# ETH-PHY.net
KiCad netlist of a schematic drawn in Altium Designer
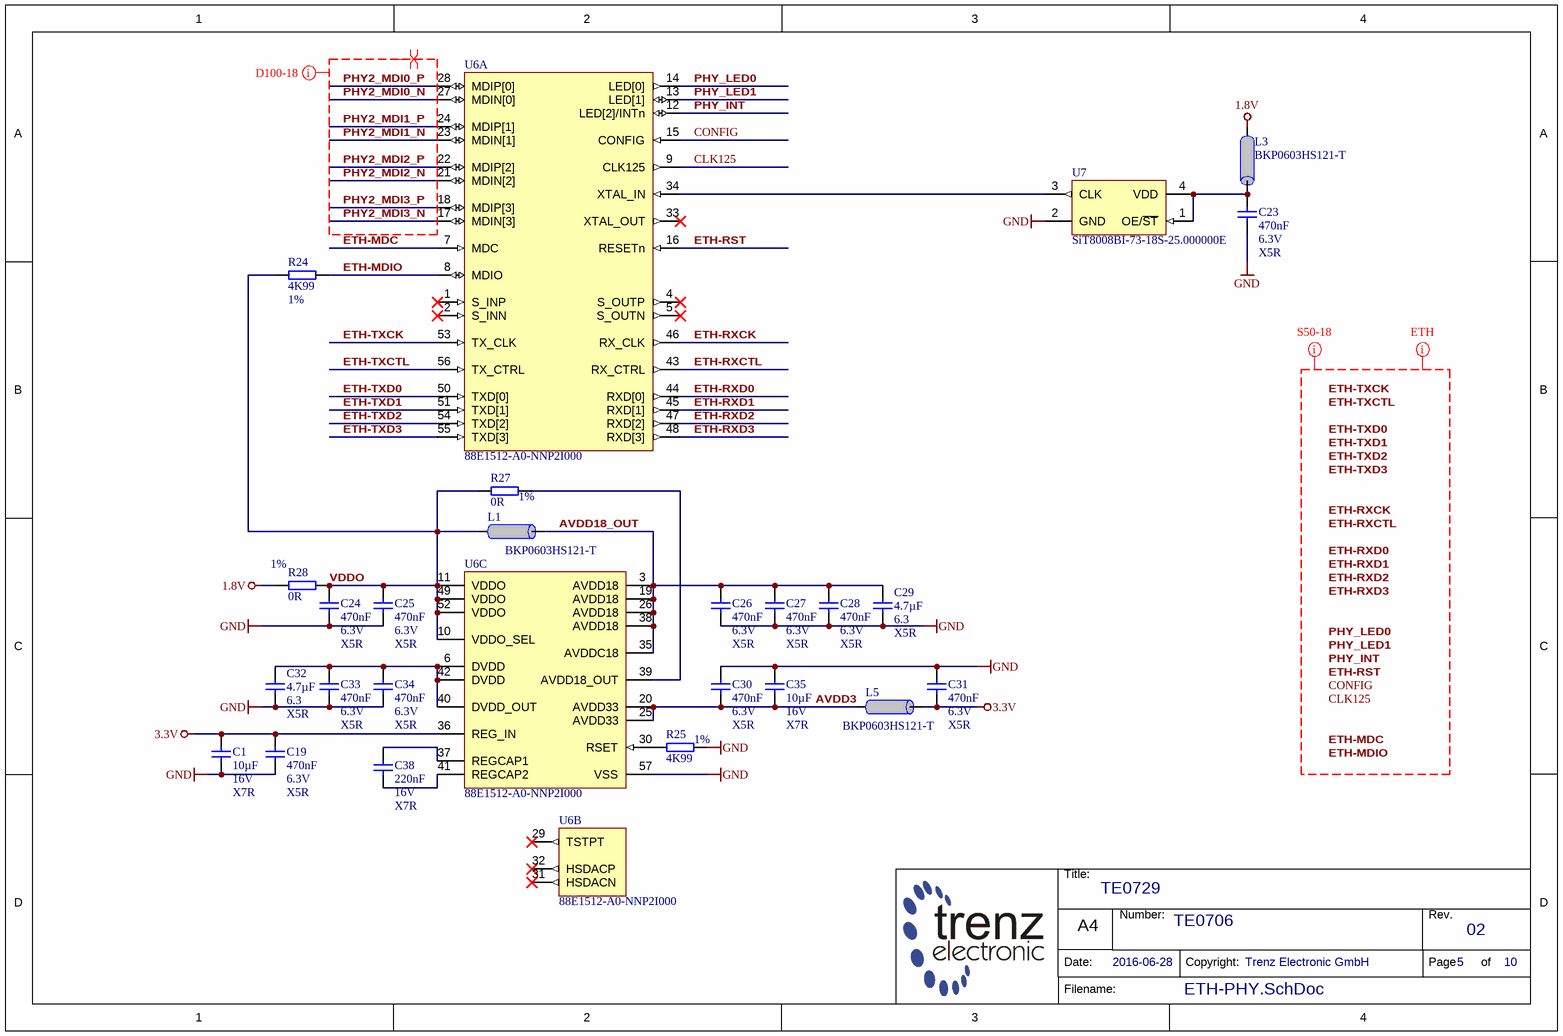
[diagram p0: ETH-PHY.SchDoc]

(export (version "E")
  (design (tool "Eeschema 10.0.6"))
  (components
    (comp (ref "C1")
      (value "10µF")
      (footprint "CAPC2012X135N")
      (description "KON 10µF 16V X7R SMD 10%")
      (fields
        (field (name "VOLTAGE") "16V")
        (field (name "TECHNOLOGY") "X7R")
        (field (name "TOLERANCE") "10%")
      )
      (libsource (lib "TE") (part "CAP-NP"))
    )
    (comp (ref "C19")
      (value "470nF")
      (footprint "CAPC1005X55N")
      (description "KON 470nF 6,3V X5R SMD")
      (fields (field (name "VOLTAGE") "6.3V") (field (name "TECHNOLOGY") "X5R"))
      (libsource (lib "TE") (part "CAP-NP"))
    )
    (comp (ref "C23")
      (value "470nF")
      (footprint "CAPC1005X55N")
      (description "KON 470nF 6,3V X5R SMD")
      (fields (field (name "VOLTAGE") "6.3V") (field (name "TECHNOLOGY") "X5R"))
      (libsource (lib "TE") (part "CAP-NP"))
    )
    (comp (ref "C24")
      (value "470nF")
      (footprint "CAPC1005X55N")
      (description "KON 470nF 6,3V X5R SMD")
      (fields (field (name "VOLTAGE") "6.3V") (field (name "TECHNOLOGY") "X5R"))
      (libsource (lib "TE") (part "CAP-NP"))
    )
    (comp (ref "C25")
      (value "470nF")
      (footprint "CAPC1005X55N")
      (description "KON 470nF 6,3V X5R SMD")
      (fields (field (name "VOLTAGE") "6.3V") (field (name "TECHNOLOGY") "X5R"))
      (libsource (lib "TE") (part "CAP-NP"))
    )
    (comp (ref "C26")
      (value "470nF")
      (footprint "CAPC1005X55N")
      (description "KON 470nF 6,3V X5R SMD")
      (fields (field (name "VOLTAGE") "6.3V") (field (name "TECHNOLOGY") "X5R"))
      (libsource (lib "TE") (part "CAP-NP"))
    )
    (comp (ref "C27")
      (value "470nF")
      (footprint "CAPC1005X55N")
      (description "KON 470nF 6,3V X5R SMD")
      (fields (field (name "VOLTAGE") "6.3V") (field (name "TECHNOLOGY") "X5R"))
      (libsource (lib "TE") (part "CAP-NP"))
    )
    (comp (ref "C28")
      (value "470nF")
      (footprint "CAPC1005X55N")
      (description "KON 470nF 6,3V X5R SMD")
      (fields (field (name "VOLTAGE") "6.3V") (field (name "TECHNOLOGY") "X5R"))
      (libsource (lib "TE") (part "CAP-NP"))
    )
    (comp (ref "C29")
      (value "4.7µF")
      (footprint "CAPC1005X60N")
      (description "KON 4.7µF 6.3V X5R SMD 20%")
      (fields
        (field (name "VOLTAGE") "6.3")
        (field (name "TECHNOLOGY") "X5R")
        (field (name "TOLERANCE") "20%")
      )
      (libsource (lib "TE") (part "CAP-NP"))
    )
    (comp (ref "C30")
      (value "470nF")
      (footprint "CAPC1005X55N")
      (description "KON 470nF 6,3V X5R SMD")
      (fields (field (name "VOLTAGE") "6.3V") (field (name "TECHNOLOGY") "X5R"))
      (libsource (lib "TE") (part "CAP-NP"))
    )
    (comp (ref "C31")
      (value "470nF")
      (footprint "CAPC1005X55N")
      (description "KON 470nF 6,3V X5R SMD")
      (fields (field (name "VOLTAGE") "6.3V") (field (name "TECHNOLOGY") "X5R"))
      (libsource (lib "TE") (part "CAP-NP"))
    )
    (comp (ref "C32")
      (value "4.7µF")
      (footprint "CAPC1005X60N")
      (description "KON 4.7µF 6.3V X5R SMD 20%")
      (fields
        (field (name "VOLTAGE") "6.3")
        (field (name "TECHNOLOGY") "X5R")
        (field (name "TOLERANCE") "20%")
      )
      (libsource (lib "TE") (part "CAP-NP"))
    )
    (comp (ref "C33")
      (value "470nF")
      (footprint "CAPC1005X55N")
      (description "KON 470nF 6,3V X5R SMD")
      (fields (field (name "VOLTAGE") "6.3V") (field (name "TECHNOLOGY") "X5R"))
      (libsource (lib "TE") (part "CAP-NP"))
    )
    (comp (ref "C34")
      (value "470nF")
      (footprint "CAPC1005X55N")
      (description "KON 470nF 6,3V X5R SMD")
      (fields (field (name "VOLTAGE") "6.3V") (field (name "TECHNOLOGY") "X5R"))
      (libsource (lib "TE") (part "CAP-NP"))
    )
    (comp (ref "C35")
      (value "10µF")
      (footprint "CAPC2012X135N")
      (description "KON 10µF 16V X7R SMD 10%")
      (fields
        (field (name "VOLTAGE") "16V")
        (field (name "TECHNOLOGY") "X7R")
        (field (name "TOLERANCE") "10%")
      )
      (libsource (lib "TE") (part "CAP-NP"))
    )
    (comp (ref "C38")
      (value "220nF")
      (footprint "CAPC1005X55N")
      (description "KON 220nF 16V X7R SMD")
      (fields (field (name "VOLTAGE") "16V") (field (name "TECHNOLOGY") "X7R"))
      (libsource (lib "TE") (part "CAP-NP"))
    )
    (comp (ref "L1")
      (value "BKP0603HS121-T")
      (footprint "INDC0603X33N")
      (description "Ferritdurchführung SMD 0201")
      (fields (field (name "TOLERANCE") "25%"))
      (libsource (lib "TE") (part "Ferritperle"))
    )
    (comp (ref "L3")
      (value "BKP0603HS121-T")
      (footprint "INDC0603X33N")
      (description "Ferritdurchführung SMD 0201")
      (fields (field (name "TOLERANCE") "25%"))
      (libsource (lib "") (part "Ferritperle_1"))
    )
    (comp (ref "L5")
      (value "BKP0603HS121-T")
      (footprint "INDC0603X33N")
      (description "Ferritdurchführung SMD 0201")
      (fields (field (name "TOLERANCE") "25%"))
      (libsource (lib "TE") (part "Ferritperle"))
    )
    (comp (ref "R24")
      (value "4K99")
      (footprint "RESC1005X40N")
      (description "WID SMD 4K99 1% 0,063W")
      (fields (field (name "TOLERANCE") "1%"))
      (libsource (lib "TE") (part "RES"))
    )
    (comp (ref "R25")
      (value "4K99")
      (footprint "RESC1005X40N")
      (description "WID SMD 4K99 1% 0,063W")
      (fields (field (name "TOLERANCE") "1%"))
      (libsource (lib "TE") (part "RES"))
    )
    (comp (ref "R27")
      (value "0R")
      (footprint "RESC1005X40N")
      (description "WID SMD 0R")
      (fields (field (name "TOLERANCE") "1%"))
      (libsource (lib "TE") (part "RES"))
    )
    (comp (ref "R28")
      (value "0R")
      (footprint "RESC1005X40N")
      (description "WID SMD 0R")
      (fields (field (name "TOLERANCE") "1%"))
      (libsource (lib "TE") (part "RES"))
    )
    (comp (ref "U6")
      (value "88E1512-A0-NNP2I000")
      (footprint "QFN50P800X800X100-57N")
      (libsource (lib "TE") (part "88E1512"))
    )
    (comp (ref "U7")
      (value "SiT8008BI-73-18S-25.000000E")
      (footprint "2016")
      (fields (field (name "VOLTAGE") "1.8V"))
      (libsource (lib "TE") (part "SiT8103"))
    )
  )
  (nets
    (net (code "1") (name "/AVDD3") (class "Default")
      (node (ref "C30") (pin "2") (pinfunction "2_2") (pintype "passive"))
      (node (ref "C35") (pin "2") (pinfunction "2_2") (pintype "passive"))
      (node (ref "L5") (pin "1") (pinfunction "1_1") (pintype "passive"))
      (node (ref "U6") (pin "20") (pinfunction "AVDD33_20") (pintype "power_in"))
      (node (ref "U6") (pin "25") (pinfunction "AVDD33_25") (pintype "power_in"))
    )
    (net (code "2") (name "/AVDD18_OUT") (class "Default")
      (node (ref "C26") (pin "1") (pinfunction "1_1") (pintype "passive"))
      (node (ref "C27") (pin "1") (pinfunction "1_1") (pintype "passive"))
      (node (ref "C28") (pin "1") (pinfunction "1_1") (pintype "passive"))
      (node (ref "C29") (pin "1") (pinfunction "1_1") (pintype "passive"))
      (node (ref "L1") (pin "2") (pinfunction "2_2") (pintype "passive"))
      (node (ref "U6") (pin "19") (pinfunction "AVDD18_19") (pintype "power_in"))
      (node (ref "U6") (pin "26") (pinfunction "AVDD18_26") (pintype "power_in"))
      (node (ref "U6") (pin "3") (pinfunction "AVDD18_3") (pintype "power_in"))
      (node (ref "U6") (pin "35") (pinfunction "AVDDC18_35") (pintype "power_in"))
      (node (ref "U6") (pin "38") (pinfunction "AVDD18_38") (pintype "power_in"))
    )
    (net (code "3") (name "/CLK125") (class "Default")
      (node (ref "U6") (pin "9") (pinfunction "CLK125_9") (pintype "output"))
    )
    (net (code "4") (name "/CONFIG") (class "Default")
      (node (ref "U6") (pin "15") (pinfunction "CONFIG_15") (pintype "input"))
    )
    (net (code "5") (name "/ETH-MDC") (class "Default")
      (node (ref "U6") (pin "7") (pinfunction "MDC_7") (pintype "input"))
    )
    (net (code "6") (name "/ETH-MDIO") (class "Default")
      (node (ref "R24") (pin "2") (pinfunction "2_2") (pintype "passive"))
      (node (ref "U6") (pin "8") (pinfunction "MDIO_8") (pintype "bidirectional"))
    )
    (net (code "7") (name "/ETH-RST") (class "Default")
      (node (ref "U6") (pin "16") (pinfunction "RESETn_16") (pintype "input"))
    )
    (net (code "8") (name "/ETH-RXCK") (class "Default")
      (node (ref "U6") (pin "46") (pinfunction "RX_CLK_46") (pintype "output"))
    )
    (net (code "9") (name "/ETH-RXCTL") (class "Default")
      (node (ref "U6") (pin "43") (pinfunction "RX_CTRL_43") (pintype "output"))
    )
    (net (code "10") (name "/ETH-RXD0") (class "Default")
      (node (ref "U6") (pin "44") (pinfunction "RXD[0]_44") (pintype "output"))
    )
    (net (code "11") (name "/ETH-RXD1") (class "Default")
      (node (ref "U6") (pin "45") (pinfunction "RXD[1]_45") (pintype "output"))
    )
    (net (code "12") (name "/ETH-RXD2") (class "Default")
      (node (ref "U6") (pin "47") (pinfunction "RXD[2]_47") (pintype "output"))
    )
    (net (code "13") (name "/ETH-RXD3") (class "Default")
      (node (ref "U6") (pin "48") (pinfunction "RXD[3]_48") (pintype "output"))
    )
    (net (code "14") (name "/ETH-TXCK") (class "Default")
      (node (ref "U6") (pin "53") (pinfunction "TX_CLK_53") (pintype "input"))
    )
    (net (code "15") (name "/ETH-TXCTL") (class "Default")
      (node (ref "U6") (pin "56") (pinfunction "TX_CTRL_56") (pintype "input"))
    )
    (net (code "16") (name "/ETH-TXD0") (class "Default")
      (node (ref "U6") (pin "50") (pinfunction "TXD[0]_50") (pintype "input"))
    )
    (net (code "17") (name "/ETH-TXD1") (class "Default")
      (node (ref "U6") (pin "51") (pinfunction "TXD[1]_51") (pintype "input"))
    )
    (net (code "18") (name "/ETH-TXD2") (class "Default")
      (node (ref "U6") (pin "54") (pinfunction "TXD[2]_54") (pintype "input"))
    )
    (net (code "19") (name "/ETH-TXD3") (class "Default")
      (node (ref "U6") (pin "55") (pinfunction "TXD[3]_55") (pintype "input"))
    )
    (net (code "20") (name "/PHY2_MDI0_N") (class "Default")
      (node (ref "U6") (pin "27") (pinfunction "MDIN[0]_27") (pintype "bidirectional"))
    )
    (net (code "21") (name "/PHY2_MDI0_P") (class "Default")
      (node (ref "U6") (pin "28") (pinfunction "MDIP[0]_28") (pintype "bidirectional"))
    )
    (net (code "22") (name "/PHY2_MDI1_N") (class "Default")
      (node (ref "U6") (pin "23") (pinfunction "MDIN[1]_23") (pintype "bidirectional"))
    )
    (net (code "23") (name "/PHY2_MDI1_P") (class "Default")
      (node (ref "U6") (pin "24") (pinfunction "MDIP[1]_24") (pintype "bidirectional"))
    )
    (net (code "24") (name "/PHY2_MDI2_N") (class "Default")
      (node (ref "U6") (pin "21") (pinfunction "MDIN[2]_21") (pintype "bidirectional"))
    )
    (net (code "25") (name "/PHY2_MDI2_P") (class "Default")
      (node (ref "U6") (pin "22") (pinfunction "MDIP[2]_22") (pintype "bidirectional"))
    )
    (net (code "26") (name "/PHY2_MDI3_N") (class "Default")
      (node (ref "U6") (pin "17") (pinfunction "MDIN[3]_17") (pintype "bidirectional"))
    )
    (net (code "27") (name "/PHY2_MDI3_P") (class "Default")
      (node (ref "U6") (pin "18") (pinfunction "MDIP[3]_18") (pintype "bidirectional"))
    )
    (net (code "28") (name "/PHY_INT") (class "Default")
      (node (ref "U6") (pin "12") (pinfunction "LED[2]/INTn_12") (pintype "bidirectional"))
    )
    (net (code "29") (name "/PHY_LED0") (class "Default")
      (node (ref "U6") (pin "14") (pinfunction "LED[0]_14") (pintype "output"))
    )
    (net (code "30") (name "/PHY_LED1") (class "Default")
      (node (ref "U6") (pin "13") (pinfunction "LED[1]_13") (pintype "bidirectional"))
    )
    (net (code "31") (name "/VDDO") (class "Default")
      (node (ref "C24") (pin "1") (pinfunction "1_1") (pintype "passive"))
      (node (ref "C25") (pin "1") (pinfunction "1_1") (pintype "passive"))
      (node (ref "L1") (pin "1") (pinfunction "1_1") (pintype "passive"))
      (node (ref "R24") (pin "1") (pinfunction "1_1") (pintype "passive"))
      (node (ref "R27") (pin "2") (pinfunction "2_2") (pintype "passive"))
      (node (ref "R28") (pin "2") (pinfunction "2_2") (pintype "passive"))
      (node (ref "U6") (pin "10") (pinfunction "VDDO_SEL_10") (pintype "power_in"))
      (node (ref "U6") (pin "11") (pinfunction "VDDO_11") (pintype "power_in"))
      (node (ref "U6") (pin "49") (pinfunction "VDDO_49") (pintype "power_in"))
      (node (ref "U6") (pin "52") (pinfunction "VDDO_52") (pintype "power_in"))
    )
    (net (code "32") (name "1.8V") (class "Default")
      (node (ref "L3") (pin "1") (pinfunction "1_1") (pintype "passive"))
      (node (ref "R28") (pin "1") (pinfunction "1_1") (pintype "passive"))
    )
    (net (code "33") (name "3.3V") (class "Default")
      (node (ref "C1") (pin "1") (pinfunction "1_1") (pintype "passive"))
      (node (ref "C19") (pin "1") (pinfunction "1_1") (pintype "passive"))
      (node (ref "C31") (pin "2") (pinfunction "2_2") (pintype "passive"))
      (node (ref "L5") (pin "2") (pinfunction "2_2") (pintype "passive"))
      (node (ref "U6") (pin "36") (pinfunction "REG_IN_36") (pintype "power_in"))
    )
    (net (code "34") (name "GND") (class "Default")
      (node (ref "C1") (pin "2") (pinfunction "2_2") (pintype "passive"))
      (node (ref "C19") (pin "2") (pinfunction "2_2") (pintype "passive"))
      (node (ref "C23") (pin "2") (pinfunction "2_2") (pintype "passive"))
      (node (ref "C24") (pin "2") (pinfunction "2_2") (pintype "passive"))
      (node (ref "C25") (pin "2") (pinfunction "2_2") (pintype "passive"))
      (node (ref "C26") (pin "2") (pinfunction "2_2") (pintype "passive"))
      (node (ref "C27") (pin "2") (pinfunction "2_2") (pintype "passive"))
      (node (ref "C28") (pin "2") (pinfunction "2_2") (pintype "passive"))
      (node (ref "C29") (pin "2") (pinfunction "2_2") (pintype "passive"))
      (node (ref "C30") (pin "1") (pinfunction "1_1") (pintype "passive"))
      (node (ref "C31") (pin "1") (pinfunction "1_1") (pintype "passive"))
      (node (ref "C32") (pin "2") (pinfunction "2_2") (pintype "passive"))
      (node (ref "C33") (pin "2") (pinfunction "2_2") (pintype "passive"))
      (node (ref "C34") (pin "2") (pinfunction "2_2") (pintype "passive"))
      (node (ref "C35") (pin "1") (pinfunction "1_1") (pintype "passive"))
      (node (ref "R25") (pin "2") (pinfunction "2_2") (pintype "passive"))
      (node (ref "U6") (pin "57") (pinfunction "VSS_57") (pintype "power_in"))
      (node (ref "U7") (pin "2") (pinfunction "GND_2") (pintype "power_in"))
    )
    (net (code "35") (name "Net-(U6A-XTAL_IN)") (class "Default")
      (node (ref "U6") (pin "34") (pinfunction "XTAL_IN_34") (pintype "input"))
      (node (ref "U7") (pin "3") (pinfunction "CLK_3") (pintype "output"))
    )
    (net (code "36") (name "Net-(U6C-AVDD18_OUT)") (class "Default")
      (node (ref "R27") (pin "1") (pinfunction "1_1") (pintype "passive"))
      (node (ref "U6") (pin "39") (pinfunction "AVDD18_OUT_39") (pintype "power_in"))
    )
    (net (code "37") (name "Net-(U6C-DVDD_OUT)") (class "Default")
      (node (ref "C32") (pin "1") (pinfunction "1_1") (pintype "passive"))
      (node (ref "C33") (pin "1") (pinfunction "1_1") (pintype "passive"))
      (node (ref "C34") (pin "1") (pinfunction "1_1") (pintype "passive"))
      (node (ref "U6") (pin "40") (pinfunction "DVDD_OUT_40") (pintype "power_in"))
      (node (ref "U6") (pin "42") (pinfunction "DVDD_42") (pintype "power_in"))
      (node (ref "U6") (pin "6") (pinfunction "DVDD_6") (pintype "power_in"))
    )
    (net (code "38") (name "Net-(U6C-REGCAP1)") (class "Default")
      (node (ref "C38") (pin "1") (pinfunction "1_1") (pintype "passive"))
      (node (ref "U6") (pin "37") (pinfunction "REGCAP1_37") (pintype "passive"))
    )
    (net (code "39") (name "Net-(U6C-REGCAP2)") (class "Default")
      (node (ref "C38") (pin "2") (pinfunction "2_2") (pintype "passive"))
      (node (ref "U6") (pin "41") (pinfunction "REGCAP2_41") (pintype "passive"))
    )
    (net (code "40") (name "Net-(U6C-RSET)") (class "Default")
      (node (ref "R25") (pin "1") (pinfunction "1_1") (pintype "passive"))
      (node (ref "U6") (pin "30") (pinfunction "RSET_30") (pintype "input"))
    )
    (net (code "41") (name "Net-(U7-OE{slash}~{ST})") (class "Default")
      (node (ref "C23") (pin "1") (pinfunction "1_1") (pintype "passive"))
      (node (ref "L3") (pin "2") (pinfunction "2_2") (pintype "passive"))
      (node (ref "U7") (pin "1") (pinfunction "OE/~{ST}_1") (pintype "input"))
      (node (ref "U7") (pin "4") (pinfunction "VDD_4") (pintype "power_in"))
    )
    (net (code "42") (name "unconnected-(U6A-S_INN-Pad2)") (class "Default")
      (node (ref "U6") (pin "2") (pinfunction "S_INN_2") (pintype "input+no_connect"))
    )
    (net (code "43") (name "unconnected-(U6A-S_INP-Pad1)") (class "Default")
      (node (ref "U6") (pin "1") (pinfunction "S_INP_1") (pintype "input+no_connect"))
    )
    (net (code "44") (name "unconnected-(U6A-S_OUTN-Pad5)") (class "Default")
      (node (ref "U6") (pin "5") (pinfunction "S_OUTN_5") (pintype "output+no_connect"))
    )
    (net (code "45") (name "unconnected-(U6A-S_OUTP-Pad4)") (class "Default")
      (node (ref "U6") (pin "4") (pinfunction "S_OUTP_4") (pintype "output+no_connect"))
    )
    (net (code "46") (name "unconnected-(U6A-XTAL_OUT-Pad33)") (class "Default")
      (node (ref "U6") (pin "33") (pinfunction "XTAL_OUT_33") (pintype "output+no_connect"))
    )
    (net (code "47") (name "unconnected-(U6B-HSDACN-Pad31)") (class "Default")
      (node (ref "U6") (pin "31") (pinfunction "HSDACN_31") (pintype "output+no_connect"))
    )
    (net (code "48") (name "unconnected-(U6B-HSDACP-Pad32)") (class "Default")
      (node (ref "U6") (pin "32") (pinfunction "HSDACP_32") (pintype "output+no_connect"))
    )
    (net (code "49") (name "unconnected-(U6B-TSTPT-Pad29)") (class "Default")
      (node (ref "U6") (pin "29") (pinfunction "TSTPT_29") (pintype "output+no_connect"))
    )
  )
)
